# pkq.net
KiCad netlist of a schematic drawn in Altium Designer
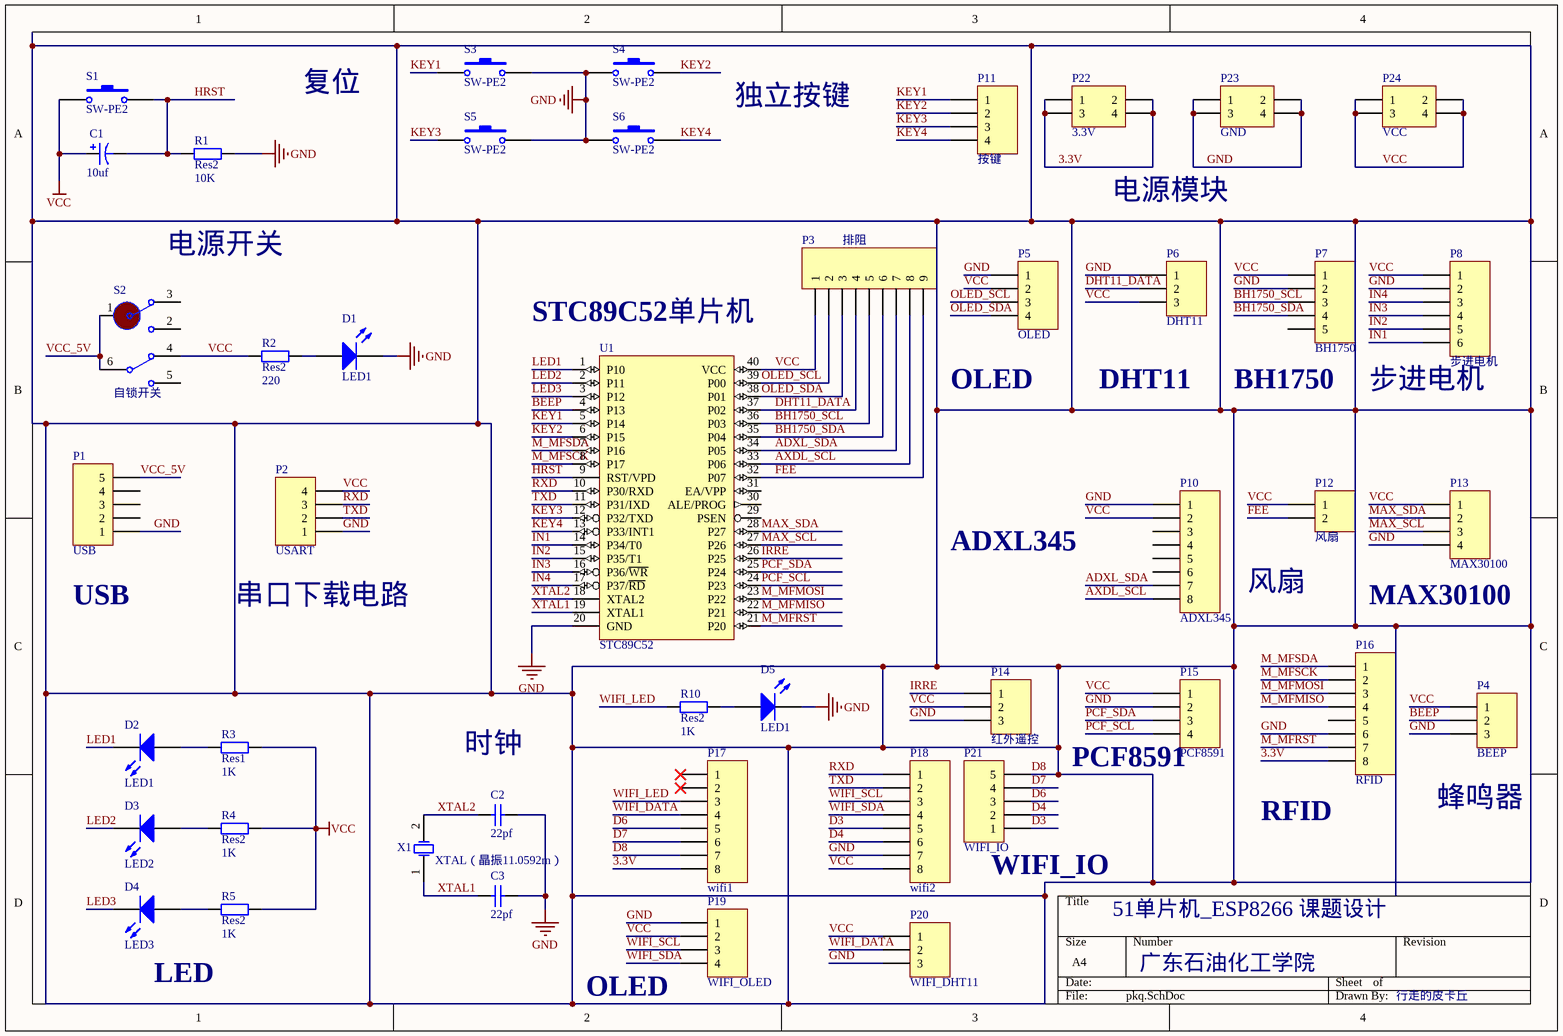
[diagram p0: pkq.SchDoc]

(export (version "E")
  (design (tool "Eeschema 10.0.6"))
  (components
    (comp (ref "C1") (value "10uf") (footprint "电解电容") (libsource (lib "51常用（2）") (part "电解电容")))
    (comp (ref "C2") (value "22pf") (footprint "瓷片电容") (libsource (lib "51常用（2）") (part "瓷片电容")))
    (comp (ref "C3") (value "22pf") (footprint "瓷片电容") (libsource (lib "51常用（2）") (part "瓷片电容")))
    (comp (ref "D1")
      (value "LED1")
      (footprint "LED-1")
      (description "Typical RED GaAs LED")
      (fields (field (name "PUBLISHER") "Altium Limited"))
      (libsource (lib "51常用（1）") (part "LED1"))
    )
    (comp (ref "D2")
      (value "LED1")
      (footprint "LED-0")
      (description "Typical INFRARED GaAs LED")
      (fields (field (name "PUBLISHER") "Altium Limited"))
      (libsource (lib "Miscellaneous Devices") (part "LED0"))
    )
    (comp (ref "D3")
      (value "LED2")
      (footprint "LED-0")
      (description "Typical INFRARED GaAs LED")
      (fields (field (name "PUBLISHER") "Altium Limited"))
      (libsource (lib "Miscellaneous Devices") (part "LED0"))
    )
    (comp (ref "D4")
      (value "LED3")
      (footprint "LED-0")
      (description "Typical INFRARED GaAs LED")
      (fields (field (name "PUBLISHER") "Altium Limited"))
      (libsource (lib "Miscellaneous Devices") (part "LED0"))
    )
    (comp (ref "D5")
      (value "LED1")
      (footprint "LED-1")
      (description "Typical RED GaAs LED")
      (fields (field (name "PUBLISHER") "Altium Limited"))
      (libsource (lib "51常用（1）") (part "LED1"))
    )
    (comp (ref "P1")
      (value "USB")
      (footprint "HDR1X5")
      (description "Header, 5-Pin")
      (fields (field (name "PUBLISHER") "Altium Limited"))
      (libsource (lib "51常用（1）") (part "Header 5"))
    )
    (comp (ref "P2")
      (value "USART")
      (footprint "HDR1X4")
      (description "Header, 4-Pin")
      (fields (field (name "PUBLISHER") "Altium Limited"))
      (libsource (lib "") (part "Header 4_1"))
    )
    (comp (ref "P3") (value "排阻") (footprint "ResPack9") (libsource (lib "51常用（2）") (part "Res Pack9")))
    (comp (ref "P4")
      (value "BEEP")
      (footprint "HDR1X3")
      (description "Header, 3-Pin")
      (fields (field (name "PUBLISHER") "Altium Limited"))
      (libsource (lib "Miscellaneous Connectors") (part "Header 3"))
    )
    (comp (ref "P5")
      (value "OLED")
      (footprint "HDR1X4")
      (description "Header, 4-Pin")
      (fields (field (name "PUBLISHER") "Altium Limited"))
      (libsource (lib "Miscellaneous Connectors") (part "Header 4"))
    )
    (comp (ref "P6")
      (value "DHT11")
      (footprint "HDR1X3")
      (description "Header, 3-Pin")
      (fields (field (name "PUBLISHER") "Altium Limited"))
      (libsource (lib "Miscellaneous Connectors") (part "Header 3"))
    )
    (comp (ref "P7")
      (value "BH1750")
      (footprint "HDR1X5")
      (description "Header, 5-Pin")
      (fields (field (name "PUBLISHER") "Altium Limited"))
      (libsource (lib "Miscellaneous Connectors") (part "Header 5"))
    )
    (comp (ref "P8")
      (value "步进电机")
      (footprint "HDR1X6")
      (description "Header, 6-Pin")
      (fields (field (name "PUBLISHER") "Altium Limited"))
      (libsource (lib "Miscellaneous Connectors") (part "Header 6"))
    )
    (comp (ref "P10")
      (value "ADXL345")
      (footprint "HDR1X8")
      (description "Header, 8-Pin")
      (fields (field (name "PUBLISHER") "Altium Limited"))
      (libsource (lib "Miscellaneous Connectors") (part "Header 8"))
    )
    (comp (ref "P11")
      (value "按键")
      (footprint "HDR1X4")
      (description "Header, 4-Pin")
      (fields (field (name "PUBLISHER") "Altium Limited"))
      (libsource (lib "Miscellaneous Connectors") (part "Header 4"))
    )
    (comp (ref "P12")
      (value "风扇")
      (footprint "HDR1X2")
      (description "Header, 2-Pin")
      (fields (field (name "PUBLISHER") "Altium Limited"))
      (libsource (lib "Miscellaneous Connectors") (part "Header 2"))
    )
    (comp (ref "P13")
      (value "MAX30100")
      (footprint "HDR1X4")
      (description "Header, 4-Pin")
      (fields (field (name "PUBLISHER") "Altium Limited"))
      (libsource (lib "Miscellaneous Connectors") (part "Header 4"))
    )
    (comp (ref "P14")
      (value "红外遥控")
      (footprint "HDR1X3")
      (description "Header, 3-Pin")
      (fields (field (name "PUBLISHER") "Altium Limited"))
      (libsource (lib "Miscellaneous Connectors") (part "Header 3"))
    )
    (comp (ref "P15")
      (value "PCF8591")
      (footprint "HDR1X4")
      (description "Header, 4-Pin")
      (fields (field (name "PUBLISHER") "Altium Limited"))
      (libsource (lib "Miscellaneous Connectors") (part "Header 4"))
    )
    (comp (ref "P16")
      (value "RFID")
      (footprint "HDR1X8")
      (description "Header, 8-Pin")
      (fields (field (name "PUBLISHER") "Altium Limited"))
      (libsource (lib "Miscellaneous Connectors") (part "Header 8"))
    )
    (comp (ref "P17")
      (value "wifi1")
      (footprint "HDR1X8")
      (description "Header, 8-Pin")
      (fields (field (name "PUBLISHER") "Altium Limited"))
      (libsource (lib "Miscellaneous Connectors") (part "Header 8"))
    )
    (comp (ref "P18")
      (value "wifi2")
      (footprint "HDR1X8")
      (description "Header, 8-Pin")
      (fields (field (name "PUBLISHER") "Altium Limited"))
      (libsource (lib "Miscellaneous Connectors") (part "Header 8"))
    )
    (comp (ref "P19")
      (value "WIFI_OLED")
      (footprint "HDR1X4")
      (description "Header, 4-Pin")
      (fields (field (name "PUBLISHER") "Altium Limited"))
      (libsource (lib "Miscellaneous Connectors") (part "Header 4"))
    )
    (comp (ref "P20")
      (value "WIFI_DHT11")
      (footprint "HDR1X3")
      (description "Header, 3-Pin")
      (fields (field (name "PUBLISHER") "Altium Limited"))
      (libsource (lib "Miscellaneous Connectors") (part "Header 3"))
    )
    (comp (ref "P21")
      (value "WIFI_IO")
      (footprint "HDR1X5")
      (description "Header, 5-Pin")
      (fields (field (name "PUBLISHER") "Altium Limited"))
      (libsource (lib "") (part "Header 5_1"))
    )
    (comp (ref "P22")
      (value "3.3V")
      (footprint "HDR2X2")
      (description "Header, 2-Pin, Dual row")
      (fields (field (name "PUBLISHER") "Altium Limited"))
      (libsource (lib "Miscellaneous Connectors") (part "Header 2X2"))
    )
    (comp (ref "P23")
      (value "GND")
      (footprint "HDR2X2")
      (description "Header, 2-Pin, Dual row")
      (fields (field (name "PUBLISHER") "Altium Limited"))
      (libsource (lib "Miscellaneous Connectors") (part "Header 2X2"))
    )
    (comp (ref "P24")
      (value "VCC")
      (footprint "HDR2X2")
      (description "Header, 2-Pin, Dual row")
      (fields (field (name "PUBLISHER") "Altium Limited"))
      (libsource (lib "Miscellaneous Connectors") (part "Header 2X2"))
    )
    (comp (ref "R1")
      (value "Res2")
      (footprint "AXIAL-0.4")
      (description "Resistor")
      (fields (field (name "ALTIUM_VALUE") "10K") (field (name "PUBLISHER") "Altium Limited"))
      (libsource (lib "Miscellaneous Devices") (part "Res2"))
    )
    (comp (ref "R2")
      (value "Res2")
      (footprint "AXIAL-0.4")
      (description "Resistor")
      (fields (field (name "ALTIUM_VALUE") "220") (field (name "PUBLISHER") "Altium Limited"))
      (libsource (lib "Miscellaneous Devices") (part "Res2"))
    )
    (comp (ref "R3")
      (value "Res1")
      (footprint "AXIAL-0.4")
      (description "Resistor")
      (fields (field (name "ALTIUM_VALUE") "1K") (field (name "PUBLISHER") "Altium Limited"))
      (libsource (lib "Miscellaneous Devices") (part "Res2"))
    )
    (comp (ref "R4")
      (value "Res2")
      (footprint "AXIAL-0.4")
      (description "Resistor")
      (fields (field (name "ALTIUM_VALUE") "1K") (field (name "PUBLISHER") "Altium Limited"))
      (libsource (lib "Miscellaneous Devices") (part "Res2"))
    )
    (comp (ref "R5")
      (value "Res2")
      (footprint "AXIAL-0.4")
      (description "Resistor")
      (fields (field (name "ALTIUM_VALUE") "1K") (field (name "PUBLISHER") "Altium Limited"))
      (libsource (lib "Miscellaneous Devices") (part "Res2"))
    )
    (comp (ref "R10")
      (value "Res2")
      (footprint "AXIAL-0.4")
      (description "Resistor")
      (fields (field (name "ALTIUM_VALUE") "1K") (field (name "PUBLISHER") "Altium Limited"))
      (libsource (lib "Miscellaneous Devices") (part "Res2"))
    )
    (comp (ref "S1") (value "SW-PE2") (footprint "KEYTOUCH") (libsource (lib "51常用（2）") (part "SW-PE2")))
    (comp (ref "S2") (value "自锁开关") (footprint "自锁开关") (libsource (lib "51常用（2）") (part "自锁开关")))
    (comp (ref "S3") (value "SW-PE2") (footprint "KEYTOUCH") (libsource (lib "51常用（2）") (part "SW-PE2")))
    (comp (ref "S4") (value "SW-PE2") (footprint "KEYTOUCH") (libsource (lib "51常用（2）") (part "SW-PE2")))
    (comp (ref "S5") (value "SW-PE2") (footprint "KEYTOUCH") (libsource (lib "51常用（2）") (part "SW-PE2")))
    (comp (ref "S6") (value "SW-PE2") (footprint "KEYTOUCH") (libsource (lib "51常用（2）") (part "SW-PE2")))
    (comp (ref "U1") (value "STC89C52") (footprint "DIP40") (libsource (lib "51常用（1）") (part "STC89C52")))
    (comp (ref "X1")
      (value "XTAL（晶振11.0592m）")
      (footprint "XTAL")
      (libsource (lib "51常用（2）") (part "XTAL（晶振）"))
    )
  )
  (nets
    (net (code "1") (name "/3.3V") (class "Default")
      (node (ref "P16") (pin "8") (pinfunction "8_8") (pintype "passive"))
      (node (ref "P17") (pin "8") (pinfunction "8_8") (pintype "passive"))
      (node (ref "P22") (pin "1") (pinfunction "1_1") (pintype "passive"))
      (node (ref "P22") (pin "2") (pinfunction "2_2") (pintype "passive"))
      (node (ref "P22") (pin "3") (pinfunction "3_3") (pintype "passive"))
      (node (ref "P22") (pin "4") (pinfunction "4_4") (pintype "passive"))
    )
    (net (code "2") (name "/ADXL_SDA") (class "Default")
      (node (ref "P10") (pin "7") (pinfunction "7_7") (pintype "passive"))
      (node (ref "P3") (pin "7") (pinfunction "7_7") (pintype "passive"))
      (node (ref "U1") (pin "34") (pinfunction "P05_34") (pintype "bidirectional"))
    )
    (net (code "3") (name "/AXDL_SCL") (class "Default")
      (node (ref "P10") (pin "8") (pinfunction "8_8") (pintype "passive"))
      (node (ref "P3") (pin "8") (pinfunction "8_8") (pintype "passive"))
      (node (ref "U1") (pin "33") (pinfunction "P06_33") (pintype "bidirectional"))
    )
    (net (code "4") (name "/BEEP") (class "Default")
      (node (ref "P4") (pin "2") (pinfunction "2_2") (pintype "passive"))
      (node (ref "U1") (pin "4") (pinfunction "P13_4") (pintype "bidirectional"))
    )
    (net (code "5") (name "/BH1750_SCL") (class "Default")
      (node (ref "P3") (pin "5") (pinfunction "5_5") (pintype "passive"))
      (node (ref "P7") (pin "3") (pinfunction "3_3") (pintype "passive"))
      (node (ref "U1") (pin "36") (pinfunction "P03_36") (pintype "bidirectional"))
    )
    (net (code "6") (name "/BH1750_SDA") (class "Default")
      (node (ref "P3") (pin "6") (pinfunction "6_6") (pintype "passive"))
      (node (ref "P7") (pin "4") (pinfunction "4_4") (pintype "passive"))
      (node (ref "U1") (pin "35") (pinfunction "P04_35") (pintype "bidirectional"))
    )
    (net (code "7") (name "/D3") (class "Default")
      (node (ref "P18") (pin "5") (pinfunction "5_5") (pintype "passive"))
      (node (ref "P21") (pin "1") (pinfunction "1_1") (pintype "passive"))
    )
    (net (code "8") (name "/D4") (class "Default")
      (node (ref "P18") (pin "6") (pinfunction "6_6") (pintype "passive"))
      (node (ref "P21") (pin "2") (pinfunction "2_2") (pintype "passive"))
    )
    (net (code "9") (name "/D6") (class "Default")
      (node (ref "P17") (pin "5") (pinfunction "5_5") (pintype "passive"))
      (node (ref "P21") (pin "3") (pinfunction "3_3") (pintype "passive"))
    )
    (net (code "10") (name "/D7") (class "Default")
      (node (ref "P17") (pin "6") (pinfunction "6_6") (pintype "passive"))
      (node (ref "P21") (pin "4") (pinfunction "4_4") (pintype "passive"))
    )
    (net (code "11") (name "/D8") (class "Default")
      (node (ref "P17") (pin "7") (pinfunction "7_7") (pintype "passive"))
      (node (ref "P21") (pin "5") (pinfunction "5_5") (pintype "passive"))
    )
    (net (code "12") (name "/DHT11_DATA") (class "Default")
      (node (ref "P3") (pin "4") (pinfunction "4_4") (pintype "passive"))
      (node (ref "P6") (pin "2") (pinfunction "2_2") (pintype "passive"))
      (node (ref "U1") (pin "37") (pinfunction "P02_37") (pintype "bidirectional"))
    )
    (net (code "13") (name "/FEE") (class "Default")
      (node (ref "P12") (pin "2") (pinfunction "2_2") (pintype "passive"))
      (node (ref "P3") (pin "9") (pinfunction "9_9") (pintype "passive"))
      (node (ref "U1") (pin "32") (pinfunction "P07_32") (pintype "bidirectional"))
    )
    (net (code "14") (name "/HRST") (class "Default")
      (node (ref "C1") (pin "2") (pinfunction "2_2") (pintype "passive"))
      (node (ref "R1") (pin "1") (pinfunction "1_1") (pintype "passive"))
      (node (ref "S1") (pin "2") (pinfunction "2_2") (pintype "passive"))
      (node (ref "U1") (pin "9") (pinfunction "RST/VPD_9") (pintype "passive"))
    )
    (net (code "15") (name "/IN1") (class "Default")
      (node (ref "P8") (pin "6") (pinfunction "6_6") (pintype "passive"))
      (node (ref "U1") (pin "14") (pinfunction "P34/T0_14") (pintype "bidirectional"))
    )
    (net (code "16") (name "/IN2") (class "Default")
      (node (ref "P8") (pin "5") (pinfunction "5_5") (pintype "passive"))
      (node (ref "U1") (pin "15") (pinfunction "P35/T1_15") (pintype "bidirectional"))
    )
    (net (code "17") (name "/IN3") (class "Default")
      (node (ref "P8") (pin "4") (pinfunction "4_4") (pintype "passive"))
      (node (ref "U1") (pin "16") (pinfunction "P36/~{WR}_16") (pintype "bidirectional"))
    )
    (net (code "18") (name "/IN4") (class "Default")
      (node (ref "P8") (pin "3") (pinfunction "3_3") (pintype "passive"))
      (node (ref "U1") (pin "17") (pinfunction "P37/~{RD}_17") (pintype "bidirectional"))
    )
    (net (code "19") (name "/IRRE") (class "Default")
      (node (ref "P14") (pin "1") (pinfunction "1_1") (pintype "passive"))
      (node (ref "U1") (pin "26") (pinfunction "P25_26") (pintype "bidirectional"))
    )
    (net (code "20") (name "/KEY1") (class "Default")
      (node (ref "P11") (pin "1") (pinfunction "1_1") (pintype "passive"))
      (node (ref "S3") (pin "1") (pinfunction "1_1") (pintype "passive"))
      (node (ref "U1") (pin "5") (pinfunction "P14_5") (pintype "bidirectional"))
    )
    (net (code "21") (name "/KEY2") (class "Default")
      (node (ref "P11") (pin "2") (pinfunction "2_2") (pintype "passive"))
      (node (ref "S4") (pin "2") (pinfunction "2_2") (pintype "passive"))
      (node (ref "U1") (pin "6") (pinfunction "P15_6") (pintype "bidirectional"))
    )
    (net (code "22") (name "/KEY3") (class "Default")
      (node (ref "P11") (pin "3") (pinfunction "3_3") (pintype "passive"))
      (node (ref "S5") (pin "1") (pinfunction "1_1") (pintype "passive"))
      (node (ref "U1") (pin "12") (pinfunction "P32/TXD_12") (pintype "bidirectional"))
    )
    (net (code "23") (name "/KEY4") (class "Default")
      (node (ref "P11") (pin "4") (pinfunction "4_4") (pintype "passive"))
      (node (ref "S6") (pin "2") (pinfunction "2_2") (pintype "passive"))
      (node (ref "U1") (pin "13") (pinfunction "P33/INT1_13") (pintype "bidirectional"))
    )
    (net (code "24") (name "/LED1") (class "Default")
      (node (ref "D2") (pin "2") (pinfunction "K_2") (pintype "passive"))
      (node (ref "U1") (pin "1") (pinfunction "P10_1") (pintype "bidirectional"))
    )
    (net (code "25") (name "/LED2") (class "Default")
      (node (ref "D3") (pin "2") (pinfunction "K_2") (pintype "passive"))
      (node (ref "U1") (pin "2") (pinfunction "P11_2") (pintype "bidirectional"))
    )
    (net (code "26") (name "/LED3") (class "Default")
      (node (ref "D4") (pin "2") (pinfunction "K_2") (pintype "passive"))
      (node (ref "U1") (pin "3") (pinfunction "P12_3") (pintype "bidirectional"))
    )
    (net (code "27") (name "/MAX_SCL") (class "Default")
      (node (ref "P13") (pin "3") (pinfunction "3_3") (pintype "passive"))
      (node (ref "U1") (pin "27") (pinfunction "P26_27") (pintype "bidirectional"))
    )
    (net (code "28") (name "/MAX_SDA") (class "Default")
      (node (ref "P13") (pin "2") (pinfunction "2_2") (pintype "passive"))
      (node (ref "U1") (pin "28") (pinfunction "P27_28") (pintype "bidirectional"))
    )
    (net (code "29") (name "/M_MFMISO") (class "Default")
      (node (ref "P16") (pin "4") (pinfunction "4_4") (pintype "passive"))
      (node (ref "U1") (pin "22") (pinfunction "P21_22") (pintype "bidirectional"))
    )
    (net (code "30") (name "/M_MFMOSI") (class "Default")
      (node (ref "P16") (pin "3") (pinfunction "3_3") (pintype "passive"))
      (node (ref "U1") (pin "23") (pinfunction "P22_23") (pintype "bidirectional"))
    )
    (net (code "31") (name "/M_MFRST") (class "Default")
      (node (ref "P16") (pin "7") (pinfunction "7_7") (pintype "passive"))
      (node (ref "U1") (pin "21") (pinfunction "P20_21") (pintype "bidirectional"))
    )
    (net (code "32") (name "/M_MFSCK") (class "Default")
      (node (ref "P16") (pin "2") (pinfunction "2_2") (pintype "passive"))
      (node (ref "U1") (pin "8") (pinfunction "P17_8") (pintype "bidirectional"))
    )
    (net (code "33") (name "/M_MFSDA") (class "Default")
      (node (ref "P16") (pin "1") (pinfunction "1_1") (pintype "passive"))
      (node (ref "U1") (pin "7") (pinfunction "P16_7") (pintype "bidirectional"))
    )
    (net (code "34") (name "/OLED_SCL") (class "Default")
      (node (ref "P3") (pin "2") (pinfunction "2_2") (pintype "passive"))
      (node (ref "P5") (pin "3") (pinfunction "3_3") (pintype "passive"))
      (node (ref "U1") (pin "39") (pinfunction "P00_39") (pintype "bidirectional"))
    )
    (net (code "35") (name "/OLED_SDA") (class "Default")
      (node (ref "P3") (pin "3") (pinfunction "3_3") (pintype "passive"))
      (node (ref "P5") (pin "4") (pinfunction "4_4") (pintype "passive"))
      (node (ref "U1") (pin "38") (pinfunction "P01_38") (pintype "bidirectional"))
    )
    (net (code "36") (name "/PCF_SCL") (class "Default")
      (node (ref "P15") (pin "4") (pinfunction "4_4") (pintype "passive"))
      (node (ref "U1") (pin "24") (pinfunction "P23_24") (pintype "bidirectional"))
    )
    (net (code "37") (name "/PCF_SDA") (class "Default")
      (node (ref "P15") (pin "3") (pinfunction "3_3") (pintype "passive"))
      (node (ref "U1") (pin "25") (pinfunction "P24_25") (pintype "bidirectional"))
    )
    (net (code "38") (name "/RXD") (class "Default")
      (node (ref "P18") (pin "1") (pinfunction "1_1") (pintype "passive"))
      (node (ref "P2") (pin "3") (pinfunction "3_3") (pintype "passive"))
      (node (ref "U1") (pin "10") (pinfunction "P30/RXD_10") (pintype "bidirectional"))
    )
    (net (code "39") (name "/TXD") (class "Default")
      (node (ref "P18") (pin "2") (pinfunction "2_2") (pintype "passive"))
      (node (ref "P2") (pin "2") (pinfunction "2_2") (pintype "passive"))
      (node (ref "U1") (pin "11") (pinfunction "P31/IXD_11") (pintype "bidirectional"))
    )
    (net (code "40") (name "/VCC_5V") (class "Default")
      (node (ref "P1") (pin "5") (pinfunction "5_5") (pintype "passive"))
      (node (ref "S2") (pin "1") (pinfunction "1_1") (pintype "passive"))
      (node (ref "S2") (pin "6") (pinfunction "6_6") (pintype "passive"))
    )
    (net (code "41") (name "/WIFI_DATA") (class "Default")
      (node (ref "P17") (pin "4") (pinfunction "4_4") (pintype "passive"))
      (node (ref "P20") (pin "2") (pinfunction "2_2") (pintype "passive"))
    )
    (net (code "42") (name "/WIFI_LED") (class "Default")
      (node (ref "P17") (pin "3") (pinfunction "3_3") (pintype "passive"))
      (node (ref "R10") (pin "1") (pinfunction "1_1") (pintype "passive"))
    )
    (net (code "43") (name "/WIFI_SCL") (class "Default")
      (node (ref "P18") (pin "3") (pinfunction "3_3") (pintype "passive"))
      (node (ref "P19") (pin "3") (pinfunction "3_3") (pintype "passive"))
    )
    (net (code "44") (name "/WIFI_SDA") (class "Default")
      (node (ref "P18") (pin "4") (pinfunction "4_4") (pintype "passive"))
      (node (ref "P19") (pin "4") (pinfunction "4_4") (pintype "passive"))
    )
    (net (code "45") (name "/XTAL1") (class "Default")
      (node (ref "C3") (pin "1") (pinfunction "1_1") (pintype "passive"))
      (node (ref "U1") (pin "19") (pinfunction "XTAL1_19") (pintype "passive"))
      (node (ref "X1") (pin "1") (pinfunction "OSC1_1") (pintype "passive"))
    )
    (net (code "46") (name "/XTAL2") (class "Default")
      (node (ref "C2") (pin "1") (pinfunction "1_1") (pintype "passive"))
      (node (ref "U1") (pin "18") (pinfunction "XTAL2_18") (pintype "passive"))
      (node (ref "X1") (pin "2") (pinfunction "OSC2_2") (pintype "passive"))
    )
    (net (code "47") (name "GND") (class "Default")
      (node (ref "C2") (pin "2") (pinfunction "2_2") (pintype "passive"))
      (node (ref "C3") (pin "2") (pinfunction "2_2") (pintype "passive"))
      (node (ref "D1") (pin "2") (pinfunction "K_2") (pintype "passive"))
      (node (ref "D5") (pin "2") (pinfunction "K_2") (pintype "passive"))
      (node (ref "P1") (pin "1") (pinfunction "1_1") (pintype "passive"))
      (node (ref "P10") (pin "1") (pinfunction "1_1") (pintype "passive"))
      (node (ref "P13") (pin "4") (pinfunction "4_4") (pintype "passive"))
      (node (ref "P14") (pin "3") (pinfunction "3_3") (pintype "passive"))
      (node (ref "P15") (pin "2") (pinfunction "2_2") (pintype "passive"))
      (node (ref "P16") (pin "6") (pinfunction "6_6") (pintype "passive"))
      (node (ref "P18") (pin "7") (pinfunction "7_7") (pintype "passive"))
      (node (ref "P19") (pin "1") (pinfunction "1_1") (pintype "passive"))
      (node (ref "P2") (pin "1") (pinfunction "1_1") (pintype "passive"))
      (node (ref "P20") (pin "3") (pinfunction "3_3") (pintype "passive"))
      (node (ref "P23") (pin "1") (pinfunction "1_1") (pintype "passive"))
      (node (ref "P23") (pin "2") (pinfunction "2_2") (pintype "passive"))
      (node (ref "P23") (pin "3") (pinfunction "3_3") (pintype "passive"))
      (node (ref "P23") (pin "4") (pinfunction "4_4") (pintype "passive"))
      (node (ref "P4") (pin "3") (pinfunction "3_3") (pintype "passive"))
      (node (ref "P5") (pin "1") (pinfunction "1_1") (pintype "passive"))
      (node (ref "P6") (pin "1") (pinfunction "1_1") (pintype "passive"))
      (node (ref "P7") (pin "2") (pinfunction "2_2") (pintype "passive"))
      (node (ref "P8") (pin "2") (pinfunction "2_2") (pintype "passive"))
      (node (ref "R1") (pin "2") (pinfunction "2_2") (pintype "passive"))
      (node (ref "S3") (pin "2") (pinfunction "2_2") (pintype "passive"))
      (node (ref "S4") (pin "1") (pinfunction "1_1") (pintype "passive"))
      (node (ref "S5") (pin "2") (pinfunction "2_2") (pintype "passive"))
      (node (ref "S6") (pin "1") (pinfunction "1_1") (pintype "passive"))
      (node (ref "U1") (pin "20") (pinfunction "GND_20") (pintype "passive"))
    )
    (net (code "48") (name "Net-(D1-A)") (class "Default")
      (node (ref "D1") (pin "1") (pinfunction "A_1") (pintype "passive"))
      (node (ref "R2") (pin "2") (pinfunction "2_2") (pintype "passive"))
    )
    (net (code "49") (name "Net-(D2-A)") (class "Default")
      (node (ref "D2") (pin "1") (pinfunction "A_1") (pintype "passive"))
      (node (ref "R3") (pin "1") (pinfunction "1_1") (pintype "passive"))
    )
    (net (code "50") (name "Net-(D3-A)") (class "Default")
      (node (ref "D3") (pin "1") (pinfunction "A_1") (pintype "passive"))
      (node (ref "R4") (pin "1") (pinfunction "1_1") (pintype "passive"))
    )
    (net (code "51") (name "Net-(D4-A)") (class "Default")
      (node (ref "D4") (pin "1") (pinfunction "A_1") (pintype "passive"))
      (node (ref "R5") (pin "1") (pinfunction "1_1") (pintype "passive"))
    )
    (net (code "52") (name "Net-(D5-A)") (class "Default")
      (node (ref "D5") (pin "1") (pinfunction "A_1") (pintype "passive"))
      (node (ref "R10") (pin "2") (pinfunction "2_2") (pintype "passive"))
    )
    (net (code "53") (name "VCC") (class "Default")
      (node (ref "C1") (pin "1") (pinfunction "1_1") (pintype "passive"))
      (node (ref "P10") (pin "2") (pinfunction "2_2") (pintype "passive"))
      (node (ref "P12") (pin "1") (pinfunction "1_1") (pintype "passive"))
      (node (ref "P13") (pin "1") (pinfunction "1_1") (pintype "passive"))
      (node (ref "P14") (pin "2") (pinfunction "2_2") (pintype "passive"))
      (node (ref "P15") (pin "1") (pinfunction "1_1") (pintype "passive"))
      (node (ref "P18") (pin "8") (pinfunction "8_8") (pintype "passive"))
      (node (ref "P19") (pin "2") (pinfunction "2_2") (pintype "passive"))
      (node (ref "P2") (pin "4") (pinfunction "4_4") (pintype "passive"))
      (node (ref "P20") (pin "1") (pinfunction "1_1") (pintype "passive"))
      (node (ref "P24") (pin "1") (pinfunction "1_1") (pintype "passive"))
      (node (ref "P24") (pin "2") (pinfunction "2_2") (pintype "passive"))
      (node (ref "P24") (pin "3") (pinfunction "3_3") (pintype "passive"))
      (node (ref "P24") (pin "4") (pinfunction "4_4") (pintype "passive"))
      (node (ref "P3") (pin "1") (pinfunction "1_1") (pintype "passive"))
      (node (ref "P4") (pin "1") (pinfunction "1_1") (pintype "passive"))
      (node (ref "P5") (pin "2") (pinfunction "2_2") (pintype "passive"))
      (node (ref "P6") (pin "3") (pinfunction "3_3") (pintype "passive"))
      (node (ref "P7") (pin "1") (pinfunction "1_1") (pintype "passive"))
      (node (ref "P8") (pin "1") (pinfunction "1_1") (pintype "passive"))
      (node (ref "R2") (pin "1") (pinfunction "1_1") (pintype "passive"))
      (node (ref "R3") (pin "2") (pinfunction "2_2") (pintype "passive"))
      (node (ref "R4") (pin "2") (pinfunction "2_2") (pintype "passive"))
      (node (ref "R5") (pin "2") (pinfunction "2_2") (pintype "passive"))
      (node (ref "S1") (pin "1") (pinfunction "1_1") (pintype "passive"))
      (node (ref "S2") (pin "4") (pinfunction "4_4") (pintype "passive"))
      (node (ref "U1") (pin "40") (pinfunction "VCC_40") (pintype "bidirectional"))
    )
    (net (code "54") (name "unconnected-(P1-Pad2)") (class "Default")
      (node (ref "P1") (pin "2") (pinfunction "2_2") (pintype "passive"))
    )
    (net (code "55") (name "unconnected-(P1-Pad3)") (class "Default")
      (node (ref "P1") (pin "3") (pinfunction "3_3") (pintype "passive"))
    )
    (net (code "56") (name "unconnected-(P1-Pad4)") (class "Default")
      (node (ref "P1") (pin "4") (pinfunction "4_4") (pintype "passive"))
    )
    (net (code "57") (name "unconnected-(P7-Pad5)") (class "Default")
      (node (ref "P7") (pin "5") (pinfunction "5_5") (pintype "passive"))
    )
    (net (code "58") (name "unconnected-(P10-Pad3)") (class "Default")
      (node (ref "P10") (pin "3") (pinfunction "3_3") (pintype "passive"))
    )
    (net (code "59") (name "unconnected-(P10-Pad4)") (class "Default")
      (node (ref "P10") (pin "4") (pinfunction "4_4") (pintype "passive"))
    )
    (net (code "60") (name "unconnected-(P10-Pad5)") (class "Default")
      (node (ref "P10") (pin "5") (pinfunction "5_5") (pintype "passive"))
    )
    (net (code "61") (name "unconnected-(P10-Pad6)") (class "Default")
      (node (ref "P10") (pin "6") (pinfunction "6_6") (pintype "passive"))
    )
    (net (code "62") (name "unconnected-(P16-Pad5)") (class "Default")
      (node (ref "P16") (pin "5") (pinfunction "5_5") (pintype "passive"))
    )
    (net (code "63") (name "unconnected-(P17-Pad1)") (class "Default")
      (node (ref "P17") (pin "1") (pinfunction "1_1") (pintype "passive+no_connect"))
    )
    (net (code "64") (name "unconnected-(P17-Pad2)") (class "Default")
      (node (ref "P17") (pin "2") (pinfunction "2_2") (pintype "passive+no_connect"))
    )
    (net (code "65") (name "unconnected-(S2-Pad2)") (class "Default")
      (node (ref "S2") (pin "2") (pinfunction "2_2") (pintype "passive"))
    )
    (net (code "66") (name "unconnected-(S2-Pad3)") (class "Default")
      (node (ref "S2") (pin "3") (pinfunction "3_3") (pintype "passive"))
    )
    (net (code "67") (name "unconnected-(S2-Pad5)") (class "Default")
      (node (ref "S2") (pin "5") (pinfunction "5_5") (pintype "passive"))
    )
    (net (code "68") (name "unconnected-(U1-ALE{slash}PROG-Pad30)") (class "Default")
      (node (ref "U1") (pin "30") (pinfunction "ALE/PROG_30") (pintype "output"))
    )
    (net (code "69") (name "unconnected-(U1-EA{slash}VPP-Pad31)") (class "Default")
      (node (ref "U1") (pin "31") (pinfunction "EA/VPP_31") (pintype "bidirectional"))
    )
    (net (code "70") (name "unconnected-(U1-PSEN-Pad29)") (class "Default")
      (node (ref "U1") (pin "29") (pinfunction "PSEN_29") (pintype "passive"))
    )
  )
)
